# MRAM.net
KiCad netlist of a schematic drawn in Altium Designer
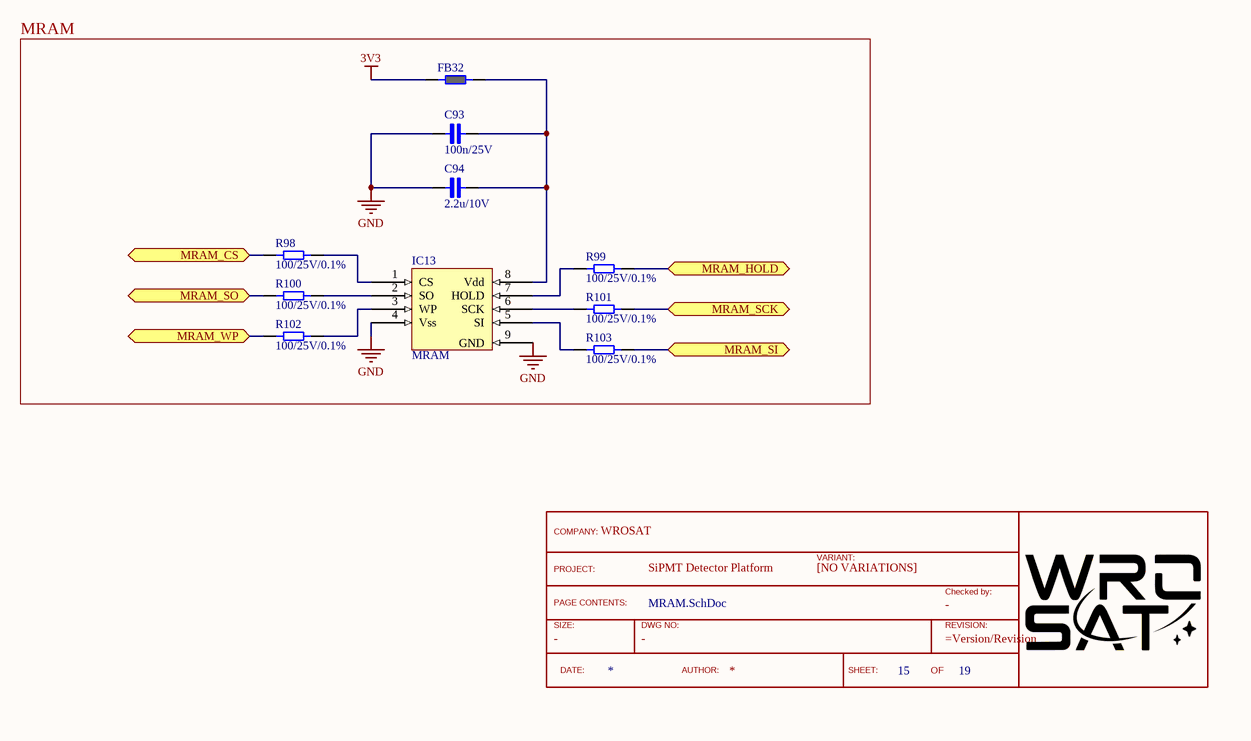
[diagram p0: MRAM.SchDoc]

(export (version "E")
  (design (tool "Eeschema 10.0.6"))
  (components
    (comp (ref "C93")
      (value "100n/25V")
      (footprint "Cap_0402")
      (description "Ceramic Capacitor 100n / 0402 / 25V / ±5%, Wurth Elektronik MLCC")
      (libsource (lib "Cubesat_lib") (part "Cap_0402_100n"))
    )
    (comp (ref "C94")
      (value "2.2u/10V")
      (footprint "CAP_0603")
      (description "Ceramic Capacitor 2.2uF / 0603 / 10V / ±5%, Wurth Elektronik MLCC")
      (libsource (lib "Cubesat_lib") (part "Cap_0603_2.2u"))
    )
    (comp (ref "FB32")
      (value "Ferrite_bead_0402")
      (footprint "FERRITE_0402")
      (description "Ferrite bead, wurth 74269241102")
      (libsource (lib "Cubesat_lib") (part "Ferrite_bead_0402"))
    )
    (comp (ref "IC13")
      (value "MRAM")
      (footprint "DFN8")
      (description "MRAM, 128Kb Serial SPI MRAM, EVERPIN technologies")
      (libsource (lib "Cubesat_lib") (part "MR25H128A"))
    )
    (comp (ref "R98")
      (value "100/25V/0.1%")
      (footprint "RES_0402")
      (description "Vishay, thin film resistor 100/25V/0.1%")
      (libsource (lib "Cubesat_lib") (part "Res_0402_100"))
    )
    (comp (ref "R99")
      (value "100/25V/0.1%")
      (footprint "RES_0402")
      (description "Vishay, thin film resistor 100/25V/0.1%")
      (libsource (lib "Cubesat_lib") (part "Res_0402_100"))
    )
    (comp (ref "R100")
      (value "100/25V/0.1%")
      (footprint "RES_0402")
      (description "Vishay, thin film resistor 100/25V/0.1%")
      (libsource (lib "Cubesat_lib") (part "Res_0402_100"))
    )
    (comp (ref "R101")
      (value "100/25V/0.1%")
      (footprint "RES_0402")
      (description "Vishay, thin film resistor 100/25V/0.1%")
      (libsource (lib "Cubesat_lib") (part "Res_0402_100"))
    )
    (comp (ref "R102")
      (value "100/25V/0.1%")
      (footprint "RES_0402")
      (description "Vishay, thin film resistor 100/25V/0.1%")
      (libsource (lib "Cubesat_lib") (part "Res_0402_100"))
    )
    (comp (ref "R103")
      (value "100/25V/0.1%")
      (footprint "RES_0402")
      (description "Vishay, thin film resistor 100/25V/0.1%")
      (libsource (lib "Cubesat_lib") (part "Res_0402_100"))
    )
  )
  (nets
    (net (code "1") (name "/MRAM_CS") (class "Default")
      (node (ref "R98") (pin "1") (pinfunction "1_1") (pintype "passive"))
    )
    (net (code "2") (name "/MRAM_HOLD") (class "Default")
      (node (ref "R99") (pin "2") (pinfunction "2_2") (pintype "passive"))
    )
    (net (code "3") (name "/MRAM_SCK") (class "Default")
      (node (ref "R101") (pin "2") (pinfunction "2_2") (pintype "passive"))
    )
    (net (code "4") (name "/MRAM_SI") (class "Default")
      (node (ref "R103") (pin "2") (pinfunction "2_2") (pintype "passive"))
    )
    (net (code "5") (name "/MRAM_SO") (class "Default")
      (node (ref "R100") (pin "1") (pinfunction "1_1") (pintype "passive"))
    )
    (net (code "6") (name "/MRAM_WP") (class "Default")
      (node (ref "R102") (pin "1") (pinfunction "1_1") (pintype "passive"))
    )
    (net (code "7") (name "3V3") (class "Default")
      (node (ref "FB32") (pin "1") (pinfunction "1_1") (pintype "passive"))
    )
    (net (code "8") (name "GND") (class "Default")
      (node (ref "C93") (pin "1") (pinfunction "1_1") (pintype "passive"))
      (node (ref "C94") (pin "1") (pinfunction "1_1") (pintype "passive"))
      (node (ref "IC13") (pin "4") (pinfunction "Vss_4") (pintype "input"))
      (node (ref "IC13") (pin "9") (pinfunction "GND_9") (pintype "input"))
    )
    (net (code "9") (name "Net-(IC13-CS)") (class "Default")
      (node (ref "IC13") (pin "1") (pinfunction "CS_1") (pintype "input"))
      (node (ref "R98") (pin "2") (pinfunction "2_2") (pintype "passive"))
    )
    (net (code "10") (name "Net-(IC13-HOLD)") (class "Default")
      (node (ref "IC13") (pin "7") (pinfunction "HOLD_7") (pintype "input"))
      (node (ref "R99") (pin "1") (pinfunction "1_1") (pintype "passive"))
    )
    (net (code "11") (name "Net-(IC13-SCK)") (class "Default")
      (node (ref "IC13") (pin "6") (pinfunction "SCK_6") (pintype "input"))
      (node (ref "R101") (pin "1") (pinfunction "1_1") (pintype "passive"))
    )
    (net (code "12") (name "Net-(IC13-SI)") (class "Default")
      (node (ref "IC13") (pin "5") (pinfunction "SI_5") (pintype "input"))
      (node (ref "R103") (pin "1") (pinfunction "1_1") (pintype "passive"))
    )
    (net (code "13") (name "Net-(IC13-SO)") (class "Default")
      (node (ref "IC13") (pin "2") (pinfunction "SO_2") (pintype "input"))
      (node (ref "R100") (pin "2") (pinfunction "2_2") (pintype "passive"))
    )
    (net (code "14") (name "Net-(IC13-Vdd)") (class "Default")
      (node (ref "C93") (pin "2") (pinfunction "2_2") (pintype "passive"))
      (node (ref "C94") (pin "2") (pinfunction "2_2") (pintype "passive"))
      (node (ref "FB32") (pin "2") (pinfunction "2_2") (pintype "passive"))
      (node (ref "IC13") (pin "8") (pinfunction "Vdd_8") (pintype "input"))
    )
    (net (code "15") (name "Net-(IC13-WP)") (class "Default")
      (node (ref "IC13") (pin "3") (pinfunction "WP_3") (pintype "input"))
      (node (ref "R102") (pin "2") (pinfunction "2_2") (pintype "passive"))
    )
  )
)
